# Sheet1.net
KiCad netlist of a schematic drawn in Altium Designer
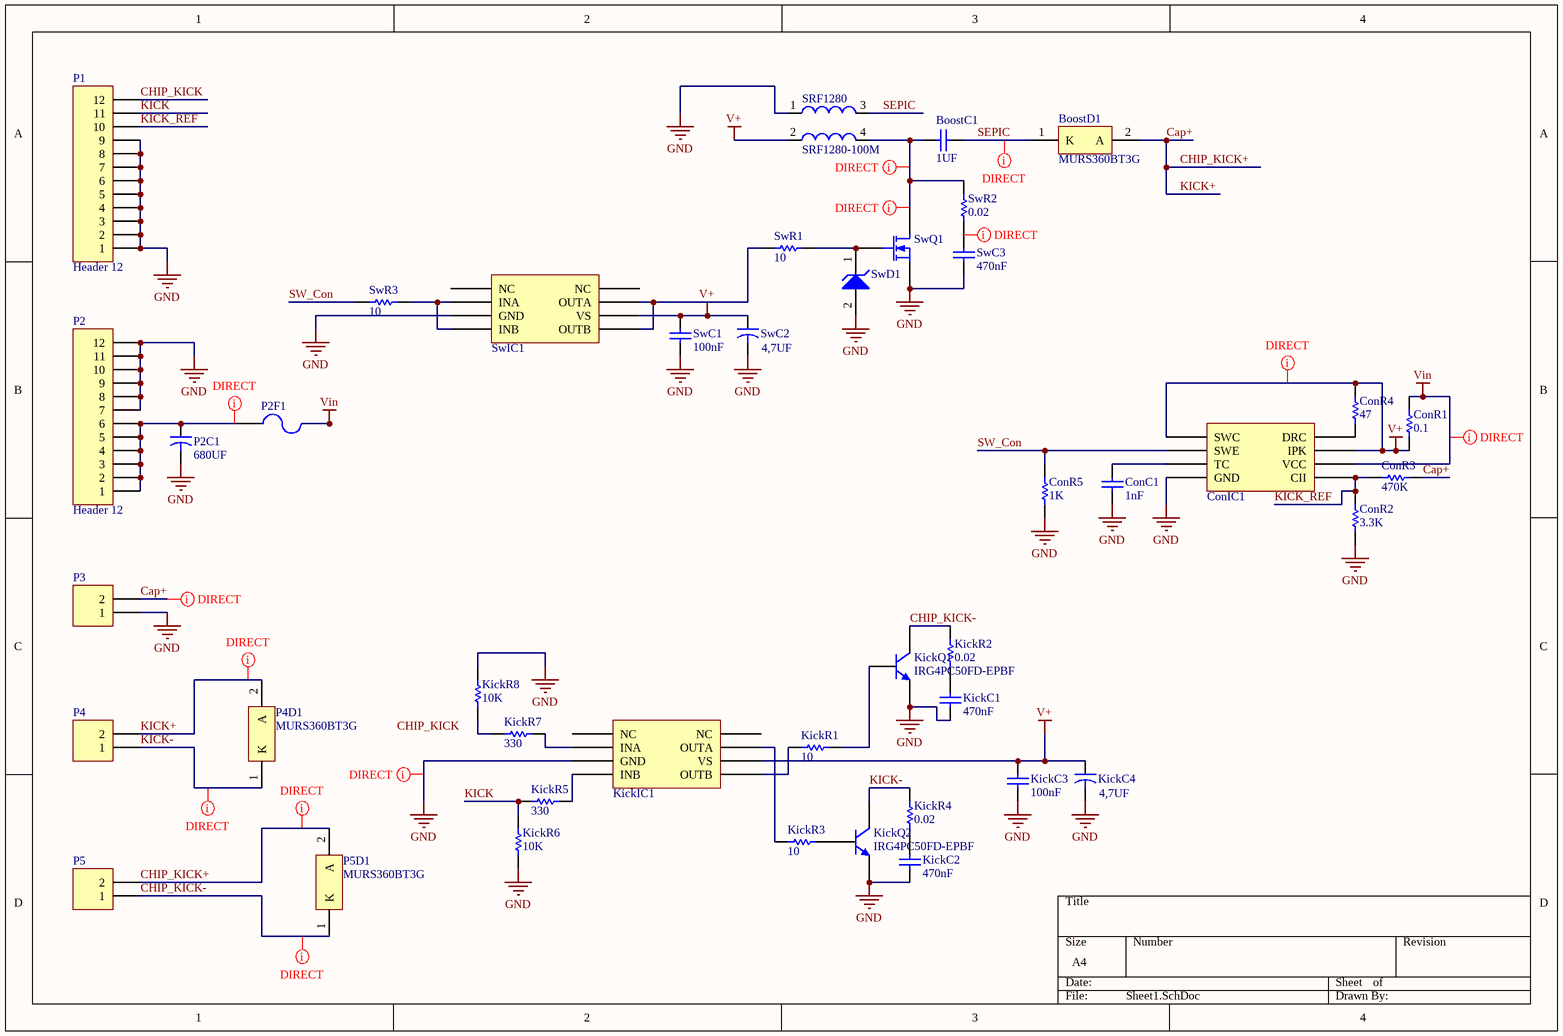
[diagram p0: Sheet1.SchDoc]

(export (version "E")
  (design (tool "Eeschema 10.0.6"))
  (components
    (comp (ref "BoostC1")
      (value "1UF")
      (footprint "CAP-2220")
      (description "1µF 450V Ceramic Capacitor X7T 2220 (5750 Metric) 0.224\" L x 0.197\" W (5.70mm x 5.00mm)")
      (fields (field (name "Comment") "CGA9P4X7T2W105M250KE"))
      (libsource (lib "Schlib1") (part "Cap 1UF 2220 450V"))
    )
    (comp (ref "BoostD1")
      (value "MURS360BT3G")
      (footprint "ONSC-SMB-2-403A-03_V")
      (description "Surface Mount Ultrafast Power Rectifier, 2-Pin SMB, Pb-Free, Tape and Reel")
      (fields (field (name "MANUFACTURER") "On Semiconductor"))
      (libsource (lib "") (part "CMP-0902-00327-1_1"))
    )
    (comp (ref "ConC1")
      (value "1nF")
      (footprint "CAP-0402")
      (description "1000pF 50V Ceramic Capacitor X7R 0402 (1005 Metric) 0.039\" L x 0.020\" W (1.00mm x 0.50mm)")
      (fields (field (name "Comment") "GRM155R71H102KA01D"))
      (libsource (lib "Schlib1") (part "Cap 1nF 0402"))
    )
    (comp (ref "ConIC1")
      (value "MC34063ACD")
      (footprint "SOIC8-STM")
      (libsource (lib "Schlib1") (part "MC34063ACD"))
    )
    (comp (ref "ConR1")
      (value "0.1")
      (footprint "RES-2512 BOURNS CRA")
      (description "RES SMD 0.1 OHM 1% 3W 2512")
      (fields (field (name "Comment") "CRA2512-FZ-R100ELF"))
      (libsource (lib "Schlib1") (part "RES 0R1 2512"))
    )
    (comp (ref "ConR2")
      (value "3.3K")
      (footprint "RES-1206")
      (description "RES SMD 3.3K OHM 5% 1/4W 1206")
      (fields (field (name "Comment") "RC1206JR-073K3L"))
      (libsource (lib "Schlib1") (part "RES 3.3K 1206"))
    )
    (comp (ref "ConR3")
      (value "470K")
      (footprint "RES-1206")
      (description "RES SMD 470K OHM 1% 1/4W 1206")
      (fields (field (name "Comment") "RC1206FR-07470KL"))
      (libsource (lib "Schlib1") (part "RES 470K 1206"))
    )
    (comp (ref "ConR4")
      (value "47")
      (footprint "RES-0402")
      (description "RES SMD 47 OHM 5% 1/16W 0402")
      (fields (field (name "Comment") "RC0402JR-0747RL"))
      (libsource (lib "Schlib1") (part "RES 47 0402"))
    )
    (comp (ref "ConR5")
      (value "1K")
      (footprint "RES-0402")
      (description "RES SMD 1K OHM 5% 1/16W 0402")
      (fields (field (name "Comment") "RC0402JR-071KL"))
      (libsource (lib "Schlib1") (part "RES 1K 0402"))
    )
    (comp (ref "KickC1")
      (value "470nF")
      (footprint "CAP-1812 TDK")
      (description "0.47µF 250V Ceramic Capacitor X7R 1812 (4532 Metric) 0.177\" L x 0.126\" W (4.50mm x 3.20mm)")
      (fields (field (name "Comment") "C4532X7R2E474K230KA"))
      (libsource (lib "Schlib1") (part "Cap 470nF 250V 1812"))
    )
    (comp (ref "KickC2")
      (value "470nF")
      (footprint "CAP-1812 TDK")
      (description "0.47µF 250V Ceramic Capacitor X7R 1812 (4532 Metric) 0.177\" L x 0.126\" W (4.50mm x 3.20mm)")
      (fields (field (name "Comment") "C4532X7R2E474K230KA"))
      (libsource (lib "Schlib1") (part "Cap 470nF 250V 1812"))
    )
    (comp (ref "KickC3")
      (value "100nF")
      (footprint "CAP-0402")
      (description "0.10µF 16V Ceramic Capacitor X7R 0402 (1005 Metric) 0.039\" L x 0.020\" W (1.00mm x 0.50mm)")
      (fields (field (name "Comment") "GRM155R71C104KA88D"))
      (libsource (lib "Schlib1") (part "Cap 100nF 0402"))
    )
    (comp (ref "KickC4")
      (value "4,7UF")
      (footprint "CAP Tant 1206 Kemet")
      (fields (field (name "Comment") "T491A475M025AT"))
      (libsource (lib "Schlib1") (part "Cap Tant 4,7UF 1206"))
    )
    (comp (ref "KickIC1")
      (value "IR4427STRPBF")
      (footprint "SOIC8-INFINEON")
      (description "IC DRIVER DUAL LOW SIDE 8SOIC")
      (libsource (lib "Schlib1") (part "IR4427"))
    )
    (comp (ref "KickQ1")
      (value "IRG4PC50FD-EPBF")
      (footprint "TO-247AC")
      (description "IGBT 600V 70A 200W TO247AD")
      (libsource (lib "Schlib1") (part "IRG4PC50FD"))
    )
    (comp (ref "KickQ2")
      (value "IRG4PC50FD-EPBF")
      (footprint "TO-247AC")
      (description "IGBT 600V 70A 200W TO247AD")
      (libsource (lib "Schlib1") (part "IRG4PC50FD"))
    )
    (comp (ref "KickR1")
      (value "10")
      (footprint "RES-0402")
      (description "RES SMD 10 OHM 5% 1/16W 0402")
      (fields (field (name "Comment") "RC0402JR-0710RL"))
      (libsource (lib "Schlib1") (part "RES 10 0402"))
    )
    (comp (ref "KickR2")
      (value "0.02")
      (footprint "RES-1206")
      (description "RES SMD 0.02 OHM 1% 1/4W 1206")
      (fields (field (name "Comment") "PF1206FRF070R02L"))
      (libsource (lib "Schlib1") (part "RES 0R02 1206"))
    )
    (comp (ref "KickR3")
      (value "10")
      (footprint "RES-0402")
      (description "RES SMD 10 OHM 5% 1/16W 0402")
      (fields (field (name "Comment") "RC0402JR-0710RL"))
      (libsource (lib "Schlib1") (part "RES 10 0402"))
    )
    (comp (ref "KickR4")
      (value "0.02")
      (footprint "RES-1206")
      (description "RES SMD 0.02 OHM 1% 1/4W 1206")
      (fields (field (name "Comment") "PF1206FRF070R02L"))
      (libsource (lib "Schlib1") (part "RES 0R02 1206"))
    )
    (comp (ref "KickR5")
      (value "330")
      (footprint "RES-0402")
      (description "RES SMD 330 OHM 5% 1/16W 0402")
      (fields (field (name "Comment") "RC0402JR-07330RL"))
      (libsource (lib "Schlib1") (part "RES 330 0402"))
    )
    (comp (ref "KickR6")
      (value "10K")
      (footprint "RES-0402")
      (description "RES SMD 10K OHM 5% 1/16W 0402")
      (fields (field (name "Comment") "RC0402JR-0710KL"))
      (libsource (lib "Schlib1") (part "RES 10K 0402"))
    )
    (comp (ref "KickR7")
      (value "330")
      (footprint "RES-0402")
      (description "RES SMD 330 OHM 5% 1/16W 0402")
      (fields (field (name "Comment") "RC0402JR-07330RL"))
      (libsource (lib "Schlib1") (part "RES 330 0402"))
    )
    (comp (ref "KickR8")
      (value "10K")
      (footprint "RES-0402")
      (description "RES SMD 10K OHM 5% 1/16W 0402")
      (fields (field (name "Comment") "RC0402JR-0710KL"))
      (libsource (lib "Schlib1") (part "RES 10K 0402"))
    )
    (comp (ref "P1")
      (value "Header 12")
      (footprint "HDR1X12")
      (description "Header, 12-Pin")
      (fields (field (name "PUBLISHER") "Altium Limited"))
      (libsource (lib "Miscellaneous Connectors") (part "Header 12"))
    )
    (comp (ref "P2")
      (value "Header 12")
      (footprint "HDR1X12")
      (description "Header, 12-Pin")
      (fields (field (name "PUBLISHER") "Altium Limited"))
      (libsource (lib "Miscellaneous Connectors") (part "Header 12"))
    )
    (comp (ref "P2C1")
      (value "680UF")
      (footprint "Cap Al Size G - Panasonic")
      (description "Aluminum Electrolytic Capacitors - SMD Al Lytic Cap SMT FK Series 105C")
      (fields (field (name "Comment") "EEE-FK1C681GP"))
      (libsource (lib "Schlib1") (part "CAP AL 680UF/16V"))
    )
    (comp (ref "P2F1")
      (value "MF-MSMF250/16X-2")
      (footprint "1812-MSMF Bourns2")
      (description "PTC RESETTABLE")
      (libsource (lib "Schlib1") (part "MF-MSMF250/16X"))
    )
    (comp (ref "P3")
      (value "OSTTA024163")
      (footprint "Term Block 2P")
      (description "2 Position Wire to Board Terminal Block Horizontal with Board 0.200\" (5.08mm) Through Hole")
      (libsource (lib "Schlib1") (part "Term Block 2P"))
    )
    (comp (ref "P4")
      (value "OSTTA024163")
      (footprint "Term Block 2P")
      (description "2 Position Wire to Board Terminal Block Horizontal with Board 0.200\" (5.08mm) Through Hole")
      (libsource (lib "Schlib1") (part "Term Block 2P"))
    )
    (comp (ref "P4D1")
      (value "MURS360BT3G")
      (footprint "ONSC-SMB-2-403A-03_V")
      (description "Surface Mount Ultrafast Power Rectifier, 2-Pin SMB, Pb-Free, Tape and Reel")
      (fields (field (name "MANUFACTURER") "On Semiconductor"))
      (libsource (lib "Altium Content Vault") (part "CMP-0902-00327-1"))
    )
    (comp (ref "P5")
      (value "OSTTA024163")
      (footprint "Term Block 2P")
      (description "2 Position Wire to Board Terminal Block Horizontal with Board 0.200\" (5.08mm) Through Hole")
      (libsource (lib "Schlib1") (part "Term Block 2P"))
    )
    (comp (ref "P5D1")
      (value "MURS360BT3G")
      (footprint "ONSC-SMB-2-403A-03_V")
      (description "Surface Mount Ultrafast Power Rectifier, 2-Pin SMB, Pb-Free, Tape and Reel")
      (fields (field (name "MANUFACTURER") "On Semiconductor"))
      (libsource (lib "Altium Content Vault") (part "CMP-0902-00327-1"))
    )
    (comp (ref "SRF1280")
      (value "SRF1280-100M")
      (footprint "SRF1280-100M-PCB")
      (libsource (lib "Schlib1") (part "SRF1280-100M"))
    )
    (comp (ref "SwC1")
      (value "100nF")
      (footprint "CAP-0402")
      (description "0.10µF 16V Ceramic Capacitor X7R 0402 (1005 Metric) 0.039\" L x 0.020\" W (1.00mm x 0.50mm)")
      (fields (field (name "Comment") "GRM155R71C104KA88D"))
      (libsource (lib "Schlib1") (part "Cap 100nF 0402"))
    )
    (comp (ref "SwC2")
      (value "4,7UF")
      (footprint "CAP Tant 1206 Kemet")
      (fields (field (name "Comment") "T491A475M025AT"))
      (libsource (lib "Schlib1") (part "Cap Tant 4,7UF 1206"))
    )
    (comp (ref "SwC3")
      (value "470nF")
      (footprint "CAP-1206 KEMET")
      (description "0.47µF 50V Ceramic Capacitor X8L 1206 (3216 Metric) 0.126\" L x 0.063\" W (3.20mm x 1.60mm)")
      (fields (field (name "Comment") "C1206C474K5NACTU"))
      (libsource (lib "Schlib1") (part "Cap 470nF 50V 1206"))
    )
    (comp (ref "SwD1")
      (value "MMSZ18T1G")
      (footprint "ONSC-SOD-123-2-425-04_V")
      (description "Zener Voltage Regulator, 500 mW, 2-Pin SOD-123, Pb-Free, Tape and Reel")
      (fields (field (name "MANUFACTURER") "On Semiconductor"))
      (libsource (lib "Altium Content Vault") (part "CMP-1060-00279-1"))
    )
    (comp (ref "SwIC1")
      (value "IR4427STRPBF")
      (footprint "SOIC8-INFINEON")
      (description "IC DRIVER DUAL LOW SIDE 8SOIC")
      (libsource (lib "Schlib1") (part "IR4427"))
    )
    (comp (ref "SwQ1")
      (value "SUM45N25-58-E3")
      (footprint "TO-263 Vishay")
      (description "MOSFET N-CH 250V 45A D2PAK")
      (libsource (lib "Schlib1") (part "SUM45N25"))
    )
    (comp (ref "SwR1")
      (value "10")
      (footprint "RES-0402")
      (description "RES SMD 10 OHM 5% 1/16W 0402")
      (fields (field (name "Comment") "RC0402JR-0710RL"))
      (libsource (lib "Schlib1") (part "RES 10 0402"))
    )
    (comp (ref "SwR2")
      (value "0.02")
      (footprint "RES-1206")
      (description "RES SMD 0.02 OHM 1% 1/4W 1206")
      (fields (field (name "Comment") "PF1206FRF070R02L"))
      (libsource (lib "Schlib1") (part "RES 0R02 1206"))
    )
    (comp (ref "SwR3")
      (value "10")
      (footprint "RES-0402")
      (description "RES SMD 10 OHM 5% 1/16W 0402")
      (fields (field (name "Comment") "RC0402JR-0710RL"))
      (libsource (lib "Schlib1") (part "RES 10 0402"))
    )
  )
  (nets
    (net (code "1") (name "/CHIP_KICK") (class "Default")
      (node (ref "P1") (pin "12") (pinfunction "12_12") (pintype "passive"))
    )
    (net (code "2") (name "/CHIP_KICK+") (class "Default")
      (node (ref "BoostD1") (pin "2") (pinfunction "A_2") (pintype "passive"))
      (node (ref "ConR3") (pin "2") (pinfunction "2_2") (pintype "passive"))
      (node (ref "P3") (pin "2") (pinfunction "2_2") (pintype "passive"))
      (node (ref "P4") (pin "2") (pinfunction "2_2") (pintype "passive"))
      (node (ref "P4D1") (pin "2") (pinfunction "A_2") (pintype "passive"))
      (node (ref "P5") (pin "2") (pinfunction "2_2") (pintype "passive"))
      (node (ref "P5D1") (pin "2") (pinfunction "A_2") (pintype "passive"))
    )
    (net (code "3") (name "/CHIP_KICK-") (class "Default")
      (node (ref "KickQ1") (pin "2") (pinfunction "C_2") (pintype "passive"))
      (node (ref "KickR2") (pin "2") (pinfunction "2_2") (pintype "passive"))
      (node (ref "P5") (pin "1") (pinfunction "1_1") (pintype "passive"))
      (node (ref "P5D1") (pin "1") (pinfunction "K_1") (pintype "passive"))
    )
    (net (code "4") (name "/KICK") (class "Default")
      (node (ref "KickR5") (pin "1") (pinfunction "1_1") (pintype "passive"))
      (node (ref "KickR6") (pin "2") (pinfunction "2_2") (pintype "passive"))
      (node (ref "P1") (pin "11") (pinfunction "11_11") (pintype "passive"))
    )
    (net (code "5") (name "/KICK-") (class "Default")
      (node (ref "KickQ2") (pin "2") (pinfunction "C_2") (pintype "passive"))
      (node (ref "KickR4") (pin "2") (pinfunction "2_2") (pintype "passive"))
      (node (ref "P4") (pin "1") (pinfunction "1_1") (pintype "passive"))
      (node (ref "P4D1") (pin "1") (pinfunction "K_1") (pintype "passive"))
    )
    (net (code "6") (name "/KICK_REF") (class "Default")
      (node (ref "ConIC1") (pin "5") (pinfunction "CII_5") (pintype "passive"))
      (node (ref "ConR2") (pin "2") (pinfunction "2_2") (pintype "passive"))
      (node (ref "ConR3") (pin "1") (pinfunction "1_1") (pintype "passive"))
      (node (ref "P1") (pin "10") (pinfunction "10_10") (pintype "passive"))
    )
    (net (code "7") (name "/SEPIC") (class "Default")
      (node (ref "BoostC1") (pin "2") (pinfunction "2_2") (pintype "passive"))
      (node (ref "BoostD1") (pin "1") (pinfunction "K_1") (pintype "passive"))
      (node (ref "SRF1280") (pin "3") (pinfunction "3_3") (pintype "passive"))
    )
    (net (code "8") (name "/SW_Con") (class "Default")
      (node (ref "ConIC1") (pin "2") (pinfunction "SWE_2") (pintype "passive"))
      (node (ref "ConR5") (pin "2") (pinfunction "2_2") (pintype "passive"))
      (node (ref "SwR3") (pin "1") (pinfunction "1_1") (pintype "passive"))
    )
    (net (code "9") (name "GND") (class "Default")
      (node (ref "ConC1") (pin "1") (pinfunction "1_1") (pintype "passive"))
      (node (ref "ConIC1") (pin "4") (pinfunction "GND_4") (pintype "passive"))
      (node (ref "ConR2") (pin "1") (pinfunction "1_1") (pintype "passive"))
      (node (ref "ConR5") (pin "1") (pinfunction "1_1") (pintype "passive"))
      (node (ref "KickC1") (pin "1") (pinfunction "1_1") (pintype "passive"))
      (node (ref "KickC2") (pin "1") (pinfunction "1_1") (pintype "passive"))
      (node (ref "KickC3") (pin "1") (pinfunction "1_1") (pintype "passive"))
      (node (ref "KickC4") (pin "2") (pinfunction "2_2") (pintype "passive"))
      (node (ref "KickIC1") (pin "3") (pinfunction "GND_3") (pintype "passive"))
      (node (ref "KickQ1") (pin "3") (pinfunction "E_3") (pintype "passive"))
      (node (ref "KickQ2") (pin "3") (pinfunction "E_3") (pintype "passive"))
      (node (ref "KickR6") (pin "1") (pinfunction "1_1") (pintype "passive"))
      (node (ref "KickR8") (pin "1") (pinfunction "1_1") (pintype "passive"))
      (node (ref "P1") (pin "1") (pinfunction "1_1") (pintype "passive"))
      (node (ref "P1") (pin "2") (pinfunction "2_2") (pintype "passive"))
      (node (ref "P1") (pin "3") (pinfunction "3_3") (pintype "passive"))
      (node (ref "P1") (pin "4") (pinfunction "4_4") (pintype "passive"))
      (node (ref "P1") (pin "5") (pinfunction "5_5") (pintype "passive"))
      (node (ref "P1") (pin "6") (pinfunction "6_6") (pintype "passive"))
      (node (ref "P1") (pin "7") (pinfunction "7_7") (pintype "passive"))
      (node (ref "P1") (pin "8") (pinfunction "8_8") (pintype "passive"))
      (node (ref "P1") (pin "9") (pinfunction "9_9") (pintype "passive"))
      (node (ref "P2") (pin "10") (pinfunction "10_10") (pintype "passive"))
      (node (ref "P2") (pin "11") (pinfunction "11_11") (pintype "passive"))
      (node (ref "P2") (pin "12") (pinfunction "12_12") (pintype "passive"))
      (node (ref "P2") (pin "7") (pinfunction "7_7") (pintype "passive"))
      (node (ref "P2") (pin "8") (pinfunction "8_8") (pintype "passive"))
      (node (ref "P2") (pin "9") (pinfunction "9_9") (pintype "passive"))
      (node (ref "P2C1") (pin "2") (pinfunction "2_2") (pintype "passive"))
      (node (ref "P3") (pin "1") (pinfunction "1_1") (pintype "passive"))
      (node (ref "SRF1280") (pin "1") (pinfunction "1_1") (pintype "passive"))
      (node (ref "SwC1") (pin "1") (pinfunction "1_1") (pintype "passive"))
      (node (ref "SwC2") (pin "2") (pinfunction "2_2") (pintype "passive"))
      (node (ref "SwC3") (pin "1") (pinfunction "1_1") (pintype "passive"))
      (node (ref "SwD1") (pin "2") (pinfunction "A_2") (pintype "passive"))
      (node (ref "SwIC1") (pin "3") (pinfunction "GND_3") (pintype "passive"))
      (node (ref "SwQ1") (pin "3") (pinfunction "S_3") (pintype "passive"))
    )
    (net (code "10") (name "Net-(ConIC1-DRC)") (class "Default")
      (node (ref "ConIC1") (pin "8") (pinfunction "DRC_8") (pintype "passive"))
      (node (ref "ConR4") (pin "1") (pinfunction "1_1") (pintype "passive"))
    )
    (net (code "11") (name "Net-(ConIC1-TC)") (class "Default")
      (node (ref "ConC1") (pin "2") (pinfunction "2_2") (pintype "passive"))
      (node (ref "ConIC1") (pin "3") (pinfunction "TC_3") (pintype "passive"))
    )
    (net (code "12") (name "Net-(KickC1-Pad2)") (class "Default")
      (node (ref "KickC1") (pin "2") (pinfunction "2_2") (pintype "passive"))
      (node (ref "KickR2") (pin "1") (pinfunction "1_1") (pintype "passive"))
    )
    (net (code "13") (name "Net-(KickC2-Pad2)") (class "Default")
      (node (ref "KickC2") (pin "2") (pinfunction "2_2") (pintype "passive"))
      (node (ref "KickR4") (pin "1") (pinfunction "1_1") (pintype "passive"))
    )
    (net (code "14") (name "Net-(KickIC1-INA)") (class "Default")
      (node (ref "KickIC1") (pin "2") (pinfunction "INA_2") (pintype "passive"))
      (node (ref "KickR7") (pin "2") (pinfunction "2_2") (pintype "passive"))
    )
    (net (code "15") (name "Net-(KickIC1-INB)") (class "Default")
      (node (ref "KickIC1") (pin "4") (pinfunction "INB_4") (pintype "passive"))
      (node (ref "KickR5") (pin "2") (pinfunction "2_2") (pintype "passive"))
    )
    (net (code "16") (name "Net-(KickIC1-OUTA)") (class "Default")
      (node (ref "KickIC1") (pin "7") (pinfunction "OUTA_7") (pintype "passive"))
      (node (ref "KickR3") (pin "1") (pinfunction "1_1") (pintype "passive"))
    )
    (net (code "17") (name "Net-(KickIC1-OUTB)") (class "Default")
      (node (ref "KickIC1") (pin "5") (pinfunction "OUTB_5") (pintype "passive"))
      (node (ref "KickR1") (pin "1") (pinfunction "1_1") (pintype "passive"))
    )
    (net (code "18") (name "Net-(KickQ1-B)") (class "Default")
      (node (ref "KickQ1") (pin "1") (pinfunction "B_1") (pintype "passive"))
      (node (ref "KickR1") (pin "2") (pinfunction "2_2") (pintype "passive"))
    )
    (net (code "19") (name "Net-(KickQ2-B)") (class "Default")
      (node (ref "KickQ2") (pin "1") (pinfunction "B_1") (pintype "passive"))
      (node (ref "KickR3") (pin "2") (pinfunction "2_2") (pintype "passive"))
    )
    (net (code "20") (name "Net-(KickR7-Pad1)") (class "Default")
      (node (ref "KickR7") (pin "1") (pinfunction "1_1") (pintype "passive"))
      (node (ref "KickR8") (pin "2") (pinfunction "2_2") (pintype "passive"))
    )
    (net (code "21") (name "Net-(P2-Pad1)") (class "Default")
      (node (ref "P2") (pin "1") (pinfunction "1_1") (pintype "passive"))
      (node (ref "P2") (pin "2") (pinfunction "2_2") (pintype "passive"))
      (node (ref "P2") (pin "3") (pinfunction "3_3") (pintype "passive"))
      (node (ref "P2") (pin "4") (pinfunction "4_4") (pintype "passive"))
      (node (ref "P2") (pin "5") (pinfunction "5_5") (pintype "passive"))
      (node (ref "P2") (pin "6") (pinfunction "6_6") (pintype "passive"))
      (node (ref "P2C1") (pin "1") (pinfunction "1_1") (pintype "passive"))
      (node (ref "P2F1") (pin "1") (pinfunction "1_1") (pintype "passive"))
    )
    (net (code "22") (name "Net-(SwC3-Pad2)") (class "Default")
      (node (ref "SwC3") (pin "2") (pinfunction "2_2") (pintype "passive"))
      (node (ref "SwR2") (pin "1") (pinfunction "1_1") (pintype "passive"))
    )
    (net (code "23") (name "Net-(SwD1-K)") (class "Default")
      (node (ref "SwD1") (pin "1") (pinfunction "K_1") (pintype "passive"))
      (node (ref "SwQ1") (pin "1") (pinfunction "G_1") (pintype "passive"))
      (node (ref "SwR1") (pin "2") (pinfunction "2_2") (pintype "passive"))
    )
    (net (code "24") (name "Net-(SwIC1-INA)") (class "Default")
      (node (ref "SwIC1") (pin "2") (pinfunction "INA_2") (pintype "passive"))
      (node (ref "SwIC1") (pin "4") (pinfunction "INB_4") (pintype "passive"))
      (node (ref "SwR3") (pin "2") (pinfunction "2_2") (pintype "passive"))
    )
    (net (code "25") (name "Net-(SwIC1-OUTA)") (class "Default")
      (node (ref "SwIC1") (pin "5") (pinfunction "OUTB_5") (pintype "passive"))
      (node (ref "SwIC1") (pin "7") (pinfunction "OUTA_7") (pintype "passive"))
      (node (ref "SwR1") (pin "1") (pinfunction "1_1") (pintype "passive"))
    )
    (net (code "26") (name "Net-(SwQ1-D)") (class "Default")
      (node (ref "BoostC1") (pin "1") (pinfunction "1_1") (pintype "passive"))
      (node (ref "SRF1280") (pin "4") (pinfunction "4_4") (pintype "passive"))
      (node (ref "SwQ1") (pin "2") (pinfunction "D_2") (pintype "passive"))
      (node (ref "SwR2") (pin "2") (pinfunction "2_2") (pintype "passive"))
    )
    (net (code "27") (name "V+") (class "Default")
      (node (ref "ConIC1") (pin "1") (pinfunction "SWC_1") (pintype "passive"))
      (node (ref "ConIC1") (pin "7") (pinfunction "IPK_7") (pintype "passive"))
      (node (ref "ConR1") (pin "1") (pinfunction "1_1") (pintype "passive"))
      (node (ref "ConR4") (pin "2") (pinfunction "2_2") (pintype "passive"))
      (node (ref "KickC3") (pin "2") (pinfunction "2_2") (pintype "passive"))
      (node (ref "KickC4") (pin "1") (pinfunction "1_1") (pintype "passive"))
      (node (ref "KickIC1") (pin "6") (pinfunction "VS_6") (pintype "passive"))
      (node (ref "SRF1280") (pin "2") (pinfunction "2_2") (pintype "passive"))
      (node (ref "SwC1") (pin "2") (pinfunction "2_2") (pintype "passive"))
      (node (ref "SwC2") (pin "1") (pinfunction "1_1") (pintype "passive"))
      (node (ref "SwIC1") (pin "6") (pinfunction "VS_6") (pintype "passive"))
    )
    (net (code "28") (name "Vin") (class "Default")
      (node (ref "ConIC1") (pin "6") (pinfunction "VCC_6") (pintype "passive"))
      (node (ref "ConR1") (pin "2") (pinfunction "2_2") (pintype "passive"))
      (node (ref "P2F1") (pin "2") (pinfunction "2_2") (pintype "passive"))
    )
    (net (code "29") (name "unconnected-(KickIC1-NC-Pad1)") (class "Default")
      (node (ref "KickIC1") (pin "1") (pinfunction "NC_1") (pintype "passive"))
    )
    (net (code "30") (name "unconnected-(KickIC1-NC-Pad8)") (class "Default")
      (node (ref "KickIC1") (pin "8") (pinfunction "NC_8") (pintype "passive"))
    )
    (net (code "31") (name "unconnected-(SwIC1-NC-Pad1)") (class "Default")
      (node (ref "SwIC1") (pin "1") (pinfunction "NC_1") (pintype "passive"))
    )
    (net (code "32") (name "unconnected-(SwIC1-NC-Pad8)") (class "Default")
      (node (ref "SwIC1") (pin "8") (pinfunction "NC_8") (pintype "passive"))
    )
  )
)
